# laserdriver_v3_3_laserswitch.net
KiCad netlist of a schematic drawn in EAGLE
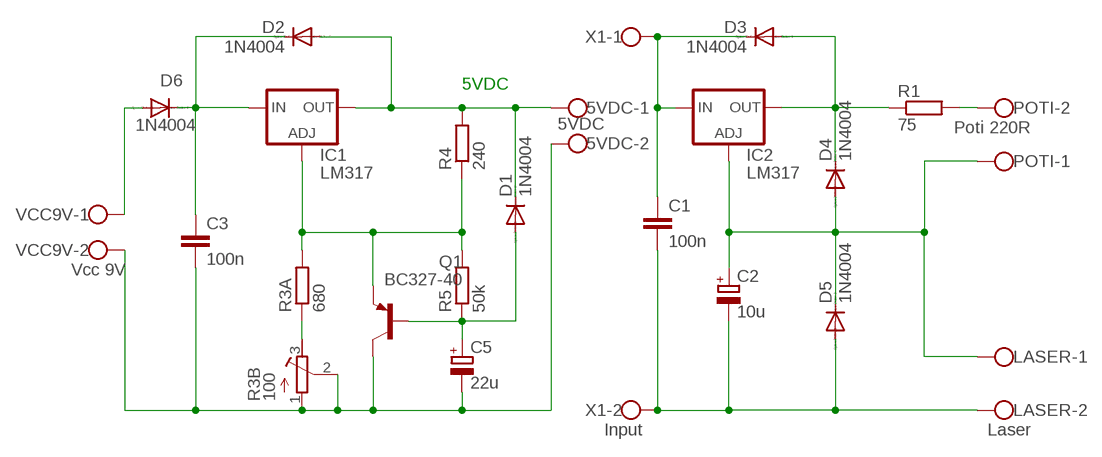
[diagram p0: schematic, sheet 1]

(export (version "E")
  (design (tool "Eeschema 10.0.6"))
  (components
    (comp (ref "5VDC")
      (value "5VDC")
      (footprint "eagle-import:W237-102")
      (fields (field (name "MPN") "237-102"))
      (libsource (lib "eagle-import") (part "W237-102"))
    )
    (comp (ref "C1")
      (value "100n")
      (footprint "eagle-import:C050-024X044")
      (libsource (lib "eagle-import") (part "C-EU050-024X044"))
    )
    (comp (ref "C2")
      (value "10u")
      (footprint "eagle-import:E2-5")
      (libsource (lib "eagle-import") (part "CPOL-EUE2-5"))
    )
    (comp (ref "C3")
      (value "100n")
      (footprint "eagle-import:C050-024X044")
      (libsource (lib "eagle-import") (part "C-EU050-024X044"))
    )
    (comp (ref "C5")
      (value "22u")
      (footprint "eagle-import:E2-5")
      (libsource (lib "eagle-import") (part "CPOL-EUE2-5"))
    )
    (comp (ref "D1")
      (value "1N4004")
      (footprint "eagle-import:DO41-10")
      (libsource (lib "eagle-import") (part "1N4004"))
    )
    (comp (ref "D2")
      (value "1N4004")
      (footprint "eagle-import:DO41-10")
      (libsource (lib "eagle-import") (part "1N4004"))
    )
    (comp (ref "D3")
      (value "1N4004")
      (footprint "eagle-import:DO41-10")
      (libsource (lib "eagle-import") (part "1N4004"))
    )
    (comp (ref "D4")
      (value "1N4004")
      (footprint "eagle-import:DO41-10")
      (libsource (lib "eagle-import") (part "1N4004"))
    )
    (comp (ref "D5")
      (value "1N4004")
      (footprint "eagle-import:DO41-10")
      (libsource (lib "eagle-import") (part "1N4004"))
    )
    (comp (ref "D6")
      (value "1N4004")
      (footprint "eagle-import:DO41-10")
      (libsource (lib "eagle-import") (part "1N4004"))
    )
    (comp (ref "IC1")
      (value "LM317")
      (footprint "eagle-import:317TS")
      (libsource (lib "eagle-import") (part "LM317TS"))
    )
    (comp (ref "IC2")
      (value "LM317")
      (footprint "eagle-import:317TS")
      (libsource (lib "eagle-import") (part "LM317TS"))
    )
    (comp (ref "LASER")
      (value "Laser")
      (footprint "eagle-import:W237-102")
      (fields (field (name "MPN") "237-102"))
      (libsource (lib "eagle-import") (part "W237-102"))
    )
    (comp (ref "POTI")
      (value "Poti 220R")
      (footprint "eagle-import:W237-102")
      (fields (field (name "MPN") "237-102"))
      (libsource (lib "eagle-import") (part "W237-102"))
    )
    (comp (ref "Q1")
      (value "BC327-40")
      (footprint "eagle-import:TO92-EBC")
      (libsource (lib "eagle-import") (part "BC327-40"))
    )
    (comp (ref "R1")
      (value "75")
      (footprint "eagle-import:0207_7")
      (libsource (lib "eagle-import") (part "R-EU_0207/7"))
    )
    (comp (ref "R3A")
      (value "680")
      (footprint "eagle-import:0207_7")
      (libsource (lib "eagle-import") (part "R-EU_0207/7"))
    )
    (comp (ref "R3B")
      (value "100")
      (footprint "eagle-import:RTRIM3296W")
      (libsource (lib "eagle-import") (part "R-TRIMM3296W"))
    )
    (comp (ref "R4")
      (value "240")
      (footprint "eagle-import:0207_7")
      (libsource (lib "eagle-import") (part "R-EU_0207/7"))
    )
    (comp (ref "R5")
      (value "50k")
      (footprint "eagle-import:0207_7")
      (libsource (lib "eagle-import") (part "R-EU_0207/7"))
    )
    (comp (ref "VCC9V")
      (value "Vcc 9V")
      (footprint "eagle-import:W237-102")
      (fields (field (name "MPN") "237-102"))
      (libsource (lib "eagle-import") (part "W237-102"))
    )
    (comp (ref "X1")
      (value "Input")
      (footprint "eagle-import:W237-102")
      (fields (field (name "MPN") "237-102"))
      (libsource (lib "eagle-import") (part "W237-102"))
    )
  )
  (nets
    (net (code "1") (name "Net-(5VDCA-KL)") (class "Default")
      (node (ref "5VDC") (pin "1") (pinfunction "KL_1") (pintype "passive"))
      (node (ref "D1") (pin "C") (pinfunction "C_C") (pintype "passive"))
      (node (ref "D2") (pin "A") (pinfunction "A_A") (pintype "passive"))
      (node (ref "IC1") (pin "2") (pinfunction "OUT_2") (pintype "passive"))
      (node (ref "R4") (pin "2") (pinfunction "2_2") (pintype "passive"))
    )
    (net (code "2") (name "Net-(5VDCB-KL)") (class "Default")
      (node (ref "5VDC") (pin "2") (pinfunction "KL_2") (pintype "passive"))
      (node (ref "C3") (pin "2") (pinfunction "2_2") (pintype "passive"))
      (node (ref "C5") (pin "-") (pinfunction "-_-") (pintype "passive"))
      (node (ref "Q1") (pin "C") (pinfunction "C_C") (pintype "passive"))
      (node (ref "R3B") (pin "1") (pinfunction "A_1") (pintype "passive"))
      (node (ref "R3B") (pin "2") (pinfunction "S_2") (pintype "passive"))
      (node (ref "VCC9V") (pin "2") (pinfunction "KL_2") (pintype "passive"))
    )
    (net (code "3") (name "Net-(C5-Pad+)") (class "Default")
      (node (ref "C5") (pin "+") (pinfunction "+_+") (pintype "passive"))
      (node (ref "D1") (pin "A") (pinfunction "A_A") (pintype "passive"))
      (node (ref "Q1") (pin "B") (pinfunction "B_B") (pintype "passive"))
      (node (ref "R5") (pin "1") (pinfunction "1_1") (pintype "passive"))
    )
    (net (code "4") (name "Net-(IC1-ADJ)") (class "Default")
      (node (ref "IC1") (pin "1") (pinfunction "ADJ_1") (pintype "input"))
      (node (ref "Q1") (pin "E") (pinfunction "E_E") (pintype "passive"))
      (node (ref "R3A") (pin "2") (pinfunction "2_2") (pintype "passive"))
      (node (ref "R4") (pin "1") (pinfunction "1_1") (pintype "passive"))
      (node (ref "R5") (pin "2") (pinfunction "2_2") (pintype "passive"))
    )
    (net (code "5") (name "Net-(IC1-IN)") (class "Default")
      (node (ref "C3") (pin "1") (pinfunction "1_1") (pintype "passive"))
      (node (ref "D2") (pin "C") (pinfunction "C_C") (pintype "passive"))
      (node (ref "D6") (pin "C") (pinfunction "C_C") (pintype "passive"))
      (node (ref "IC1") (pin "3") (pinfunction "IN_3") (pintype "input"))
    )
    (net (code "6") (name "Net-(IC2-ADJ)") (class "Default")
      (node (ref "C2") (pin "+") (pinfunction "+_+") (pintype "passive"))
      (node (ref "D4") (pin "A") (pinfunction "A_A") (pintype "passive"))
      (node (ref "D5") (pin "C") (pinfunction "C_C") (pintype "passive"))
      (node (ref "IC2") (pin "1") (pinfunction "ADJ_1") (pintype "input"))
      (node (ref "LASER") (pin "1") (pinfunction "KL_1") (pintype "passive"))
      (node (ref "POTI") (pin "1") (pinfunction "KL_1") (pintype "passive"))
    )
    (net (code "7") (name "Net-(IC2-IN)") (class "Default")
      (node (ref "C1") (pin "1") (pinfunction "1_1") (pintype "passive"))
      (node (ref "D3") (pin "C") (pinfunction "C_C") (pintype "passive"))
      (node (ref "IC2") (pin "3") (pinfunction "IN_3") (pintype "input"))
      (node (ref "X1") (pin "1") (pinfunction "KL_1") (pintype "passive"))
    )
    (net (code "8") (name "Net-(IC2-OUT)") (class "Default")
      (node (ref "D3") (pin "A") (pinfunction "A_A") (pintype "passive"))
      (node (ref "D4") (pin "C") (pinfunction "C_C") (pintype "passive"))
      (node (ref "IC2") (pin "2") (pinfunction "OUT_2") (pintype "passive"))
      (node (ref "R1") (pin "1") (pinfunction "1_1") (pintype "passive"))
    )
    (net (code "9") (name "Net-(LASERB-KL)") (class "Default")
      (node (ref "C1") (pin "2") (pinfunction "2_2") (pintype "passive"))
      (node (ref "C2") (pin "-") (pinfunction "-_-") (pintype "passive"))
      (node (ref "D5") (pin "A") (pinfunction "A_A") (pintype "passive"))
      (node (ref "LASER") (pin "2") (pinfunction "KL_2") (pintype "passive"))
      (node (ref "X1") (pin "2") (pinfunction "KL_2") (pintype "passive"))
    )
    (net (code "10") (name "Net-(POTIB-KL)") (class "Default")
      (node (ref "POTI") (pin "2") (pinfunction "KL_2") (pintype "passive"))
      (node (ref "R1") (pin "2") (pinfunction "2_2") (pintype "passive"))
    )
    (net (code "11") (name "Net-(R3B-E)") (class "Default")
      (node (ref "R3A") (pin "1") (pinfunction "1_1") (pintype "passive"))
      (node (ref "R3B") (pin "3") (pinfunction "E_3") (pintype "passive"))
    )
    (net (code "12") (name "Net-(VCC9VA-KL)") (class "Default")
      (node (ref "D6") (pin "A") (pinfunction "A_A") (pintype "passive"))
      (node (ref "VCC9V") (pin "1") (pinfunction "KL_1") (pintype "passive"))
    )
  )
)
